# User_interface.net
KiCad netlist of a schematic drawn in Altium Designer
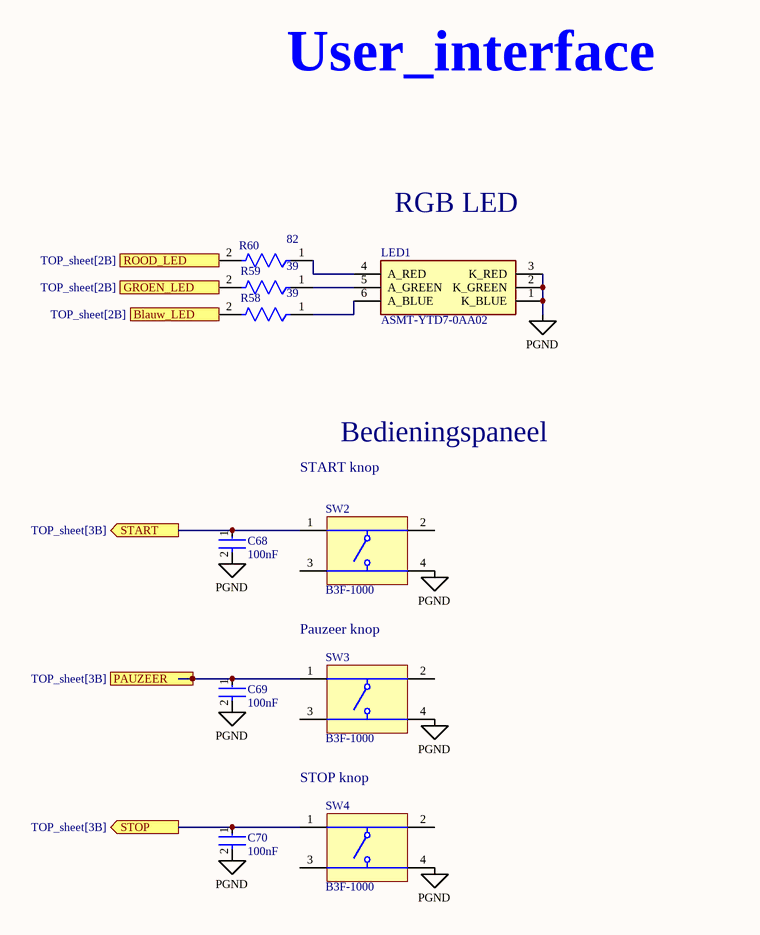
[diagram p0: User_interface.SchDoc]

(export (version "E")
  (design (tool "Eeschema 10.0.6"))
  (components
    (comp (ref "C68")
      (value "100nF")
      (footprint "FP-GRM15-MFG")
      (description "CAP CER 0.1UF 16V X7R 0402")
      (fields (field (name "MANUFACTURER PART NUMBER") "GRM155R71C104KA88D") (field (name "TOLERANCE") "10%"))
      (libsource (lib "Altium Content Vault") (part "236180d848d6139a670b325ea6854c9"))
    )
    (comp (ref "C69")
      (value "100nF")
      (footprint "FP-GRM15-MFG")
      (description "CAP CER 0.1UF 16V X7R 0402")
      (fields (field (name "MANUFACTURER PART NUMBER") "GRM155R71C104KA88D") (field (name "TOLERANCE") "10%"))
      (libsource (lib "Altium Content Vault") (part "236180d848d6139a670b325ea6854c9"))
    )
    (comp (ref "C70")
      (value "100nF")
      (footprint "FP-GRM15-MFG")
      (description "CAP CER 0.1UF 16V X7R 0402")
      (fields (field (name "MANUFACTURER PART NUMBER") "GRM155R71C104KA88D") (field (name "TOLERANCE") "10%"))
      (libsource (lib "Altium Content Vault") (part "236180d848d6139a670b325ea6854c9"))
    )
    (comp (ref "LED1")
      (value "ASMT-YTD7-0AA02")
      (footprint "SamacSys:ASMTYTD70AA02")
      (description "LED")
      (fields (field (name "MOUSER PART NUMBER") "630-ASMT-YTD7-0AA02"))
      (libsource (lib "*") (part "ASMT-YTD7-0AA02"))
    )
    (comp (ref "R58")
      (value "39")
      (footprint "FP-RC1608-IPC_B")
      (fields (field (name "TOLERANCE") "1%"))
      (libsource (lib "Altium Content Vault") (part "1029c3af85768c4190bb7ad29bc67b5"))
    )
    (comp (ref "R59")
      (value "39")
      (footprint "FP-RC1608-IPC_B")
      (fields (field (name "TOLERANCE") "1%"))
      (libsource (lib "Altium Content Vault") (part "1029c3af85768c4190bb7ad29bc67b5"))
    )
    (comp (ref "R60")
      (value "82")
      (footprint "FP-RC1608-IPC_B")
      (fields (field (name "TOLERANCE") "1%"))
      (libsource (lib "Altium Content Vault") (part "1029c3af85768c4190bb7ad29bc67b5"))
    )
    (comp (ref "SW2")
      (value "B3F-1000")
      (footprint "OMRON-B3F-1000-4_V")
      (description "Tactile Switch, SPST-NO, 0.05 A, 5 to 24 V, -25 to 70 degC, 4-Pin THD, RoHS, Bulk")
      (libsource (lib "Altium Content Vault") (part "SW-SPST-4_A"))
    )
    (comp (ref "SW3")
      (value "B3F-1000")
      (footprint "OMRON-B3F-1000-4_V")
      (description "Tactile Switch, SPST-NO, 0.05 A, 5 to 24 V, -25 to 70 degC, 4-Pin THD, RoHS, Bulk")
      (libsource (lib "Altium Content Vault") (part "SW-SPST-4_A"))
    )
    (comp (ref "SW4")
      (value "B3F-1000")
      (footprint "OMRON-B3F-1000-4_V")
      (description "Tactile Switch, SPST-NO, 0.05 A, 5 to 24 V, -25 to 70 degC, 4-Pin THD, RoHS, Bulk")
      (libsource (lib "Altium Content Vault") (part "SW-SPST-4_A"))
    )
  )
  (nets
    (net (code "1") (name "/Blauw_LED") (class "Default")
      (node (ref "R58") (pin "2") (pinfunction "2_2") (pintype "passive"))
    )
    (net (code "2") (name "/GROEN_LED") (class "Default")
      (node (ref "R59") (pin "2") (pinfunction "2_2") (pintype "passive"))
    )
    (net (code "3") (name "/PAUZEER") (class "Default")
      (node (ref "C69") (pin "1") (pinfunction "1_1") (pintype "passive"))
      (node (ref "SW3") (pin "1") (pinfunction "1_1") (pintype "passive"))
    )
    (net (code "4") (name "/ROOD_LED") (class "Default")
      (node (ref "R60") (pin "2") (pinfunction "2_2") (pintype "passive"))
    )
    (net (code "5") (name "/START") (class "Default")
      (node (ref "C68") (pin "1") (pinfunction "1_1") (pintype "passive"))
      (node (ref "SW2") (pin "1") (pinfunction "1_1") (pintype "passive"))
    )
    (net (code "6") (name "/STOP") (class "Default")
      (node (ref "C70") (pin "1") (pinfunction "1_1") (pintype "passive"))
      (node (ref "SW4") (pin "1") (pinfunction "1_1") (pintype "passive"))
    )
    (net (code "7") (name "Net-(LED1-A_BLUE)") (class "Default")
      (node (ref "LED1") (pin "6") (pinfunction "A_BLUE_6") (pintype "passive"))
      (node (ref "R58") (pin "1") (pinfunction "1_1") (pintype "passive"))
    )
    (net (code "8") (name "Net-(LED1-A_GREEN)") (class "Default")
      (node (ref "LED1") (pin "5") (pinfunction "A_GREEN_5") (pintype "passive"))
      (node (ref "R59") (pin "1") (pinfunction "1_1") (pintype "passive"))
    )
    (net (code "9") (name "Net-(LED1-A_RED)") (class "Default")
      (node (ref "LED1") (pin "4") (pinfunction "A_RED_4") (pintype "passive"))
      (node (ref "R60") (pin "1") (pinfunction "1_1") (pintype "passive"))
    )
    (net (code "10") (name "PGND") (class "Default")
      (node (ref "C68") (pin "2") (pinfunction "2_2") (pintype "passive"))
      (node (ref "C69") (pin "2") (pinfunction "2_2") (pintype "passive"))
      (node (ref "C70") (pin "2") (pinfunction "2_2") (pintype "passive"))
      (node (ref "LED1") (pin "1") (pinfunction "K_BLUE_1") (pintype "passive"))
      (node (ref "LED1") (pin "2") (pinfunction "K_GREEN_2") (pintype "passive"))
      (node (ref "LED1") (pin "3") (pinfunction "K_RED_3") (pintype "passive"))
      (node (ref "SW2") (pin "4") (pinfunction "4_4") (pintype "passive"))
      (node (ref "SW3") (pin "4") (pinfunction "4_4") (pintype "passive"))
      (node (ref "SW4") (pin "4") (pinfunction "4_4") (pintype "passive"))
    )
    (net (code "11") (name "unconnected-(SW2-Pad2)") (class "Default")
      (node (ref "SW2") (pin "2") (pinfunction "2_2") (pintype "passive"))
    )
    (net (code "12") (name "unconnected-(SW2-Pad3)") (class "Default")
      (node (ref "SW2") (pin "3") (pinfunction "3_3") (pintype "passive"))
    )
    (net (code "13") (name "unconnected-(SW3-Pad2)") (class "Default")
      (node (ref "SW3") (pin "2") (pinfunction "2_2") (pintype "passive"))
    )
    (net (code "14") (name "unconnected-(SW3-Pad3)") (class "Default")
      (node (ref "SW3") (pin "3") (pinfunction "3_3") (pintype "passive"))
    )
    (net (code "15") (name "unconnected-(SW4-Pad2)") (class "Default")
      (node (ref "SW4") (pin "2") (pinfunction "2_2") (pintype "passive"))
    )
    (net (code "16") (name "unconnected-(SW4-Pad3)") (class "Default")
      (node (ref "SW4") (pin "3") (pinfunction "3_3") (pintype "passive"))
    )
  )
)
